# IvoOerlikon2.net
KiCad netlist of a schematic drawn in EAGLE
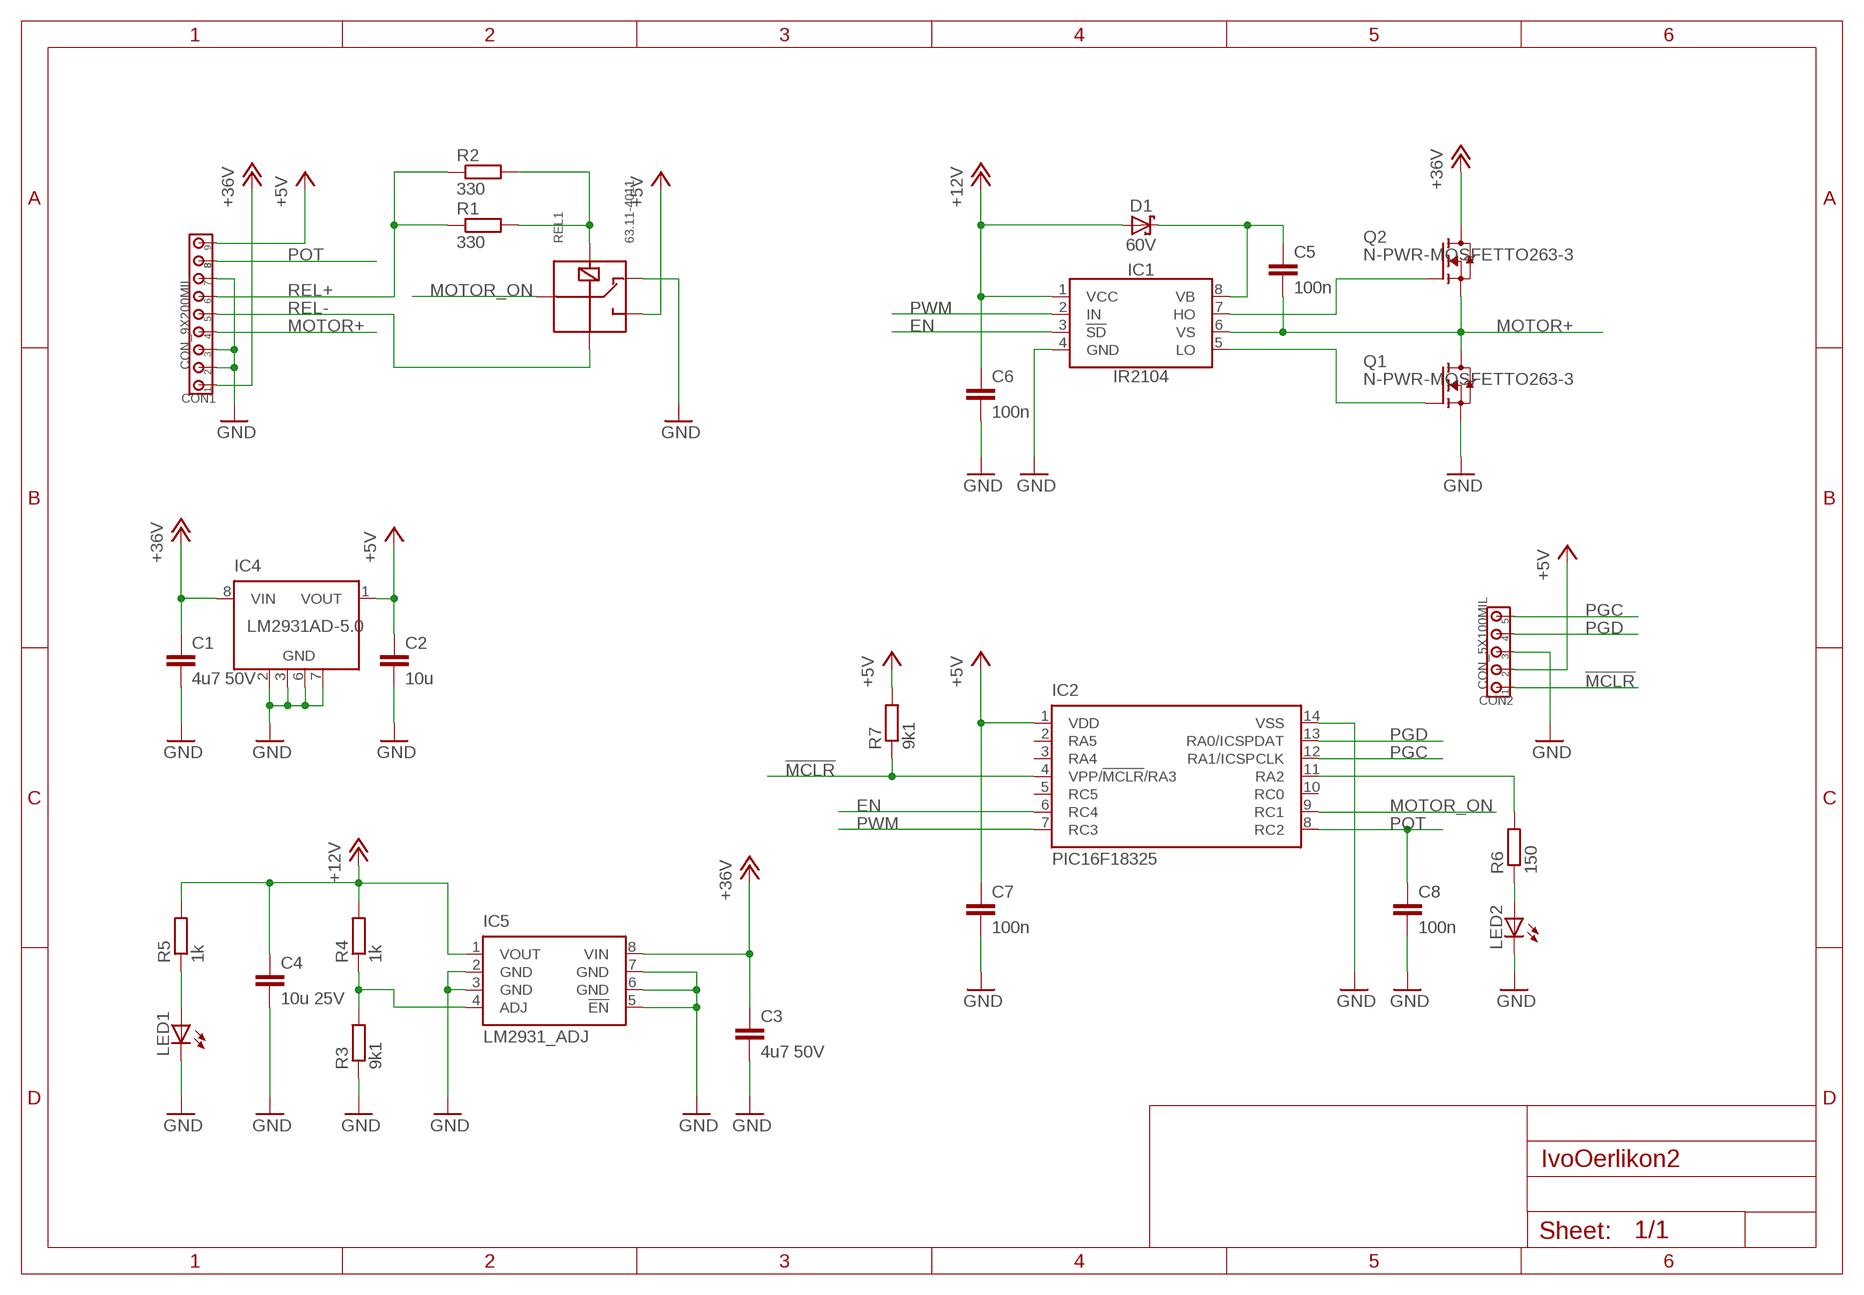
[diagram p0: schematic, sheet 1]

(export (version "E")
  (design (tool "Eeschema 10.0.6"))
  (components
    (comp (ref "C1")
      (value "4u7 50V")
      (footprint "eagle-import:C1206")
      (libsource (lib "eagle-import") (part "CC1206"))
    )
    (comp (ref "C2")
      (value "10u")
      (footprint "eagle-import:C0805")
      (libsource (lib "eagle-import") (part "CC0805"))
    )
    (comp (ref "C3")
      (value "4u7 50V")
      (footprint "eagle-import:C1206")
      (libsource (lib "eagle-import") (part "CC1206"))
    )
    (comp (ref "C4")
      (value "10u 25V")
      (footprint "eagle-import:C1206")
      (libsource (lib "eagle-import") (part "CC1206"))
    )
    (comp (ref "C5")
      (value "100n")
      (footprint "eagle-import:C0805")
      (libsource (lib "eagle-import") (part "CC0805"))
    )
    (comp (ref "C6")
      (value "100n")
      (footprint "eagle-import:C0805")
      (libsource (lib "eagle-import") (part "CC0805"))
    )
    (comp (ref "C7")
      (value "100n")
      (footprint "eagle-import:C0805")
      (libsource (lib "eagle-import") (part "CC0805"))
    )
    (comp (ref "C8")
      (value "100n")
      (footprint "eagle-import:C0805")
      (libsource (lib "eagle-import") (part "CC0805"))
    )
    (comp (ref "CON1")
      (value "CON_9X200MIL")
      (footprint "eagle-import:200MIL_9X")
      (libsource (lib "eagle-import") (part "CON_9X200MIL"))
    )
    (comp (ref "CON2")
      (value "CON_5X100MIL")
      (footprint "eagle-import:100MIL_5X")
      (libsource (lib "eagle-import") (part "CON_5X100MIL"))
    )
    (comp (ref "D1")
      (value "60V")
      (footprint "eagle-import:SOD123")
      (libsource (lib "eagle-import") (part "SCHOTTKYSOD123"))
    )
    (comp (ref "IC1")
      (value "IR2104")
      (footprint "eagle-import:SOIC8")
      (libsource (lib "eagle-import") (part "IR2104"))
    )
    (comp (ref "IC2")
      (value "PIC16F18325")
      (footprint "eagle-import:SO14")
      (libsource (lib "eagle-import") (part "PIC16F18325"))
    )
    (comp (ref "IC4")
      (value "LM2931AD-5.0")
      (footprint "eagle-import:SOIC8")
      (libsource (lib "eagle-import") (part "LM2931AD-5.0"))
    )
    (comp (ref "IC5")
      (value "LM2931_ADJ")
      (footprint "eagle-import:SOIC8")
      (libsource (lib "eagle-import") (part "LM2931_ADJ"))
    )
    (comp (ref "LED1")
      (value "LED0805")
      (footprint "eagle-import:LED0805")
      (libsource (lib "eagle-import") (part "LED0805"))
    )
    (comp (ref "LED2")
      (value "LED0805")
      (footprint "eagle-import:LED0805")
      (libsource (lib "eagle-import") (part "LED0805"))
    )
    (comp (ref "Q1")
      (value "N-PWR-MOSFETTO263-3")
      (footprint "eagle-import:TO263-3")
      (libsource (lib "eagle-import") (part "N-PWR-MOSFETTO263-3"))
    )
    (comp (ref "Q2")
      (value "N-PWR-MOSFETTO263-3")
      (footprint "eagle-import:TO263-3")
      (libsource (lib "eagle-import") (part "N-PWR-MOSFETTO263-3"))
    )
    (comp (ref "R1")
      (value "330")
      (footprint "eagle-import:R1206")
      (libsource (lib "eagle-import") (part "RESISTORR1206"))
    )
    (comp (ref "R2")
      (value "330")
      (footprint "eagle-import:R1206")
      (libsource (lib "eagle-import") (part "RESISTORR1206"))
    )
    (comp (ref "R3")
      (value "9k1")
      (footprint "eagle-import:R0805")
      (libsource (lib "eagle-import") (part "RESISTORR0805"))
    )
    (comp (ref "R4")
      (value "1k")
      (footprint "eagle-import:R0805")
      (libsource (lib "eagle-import") (part "RESISTORR0805"))
    )
    (comp (ref "R5")
      (value "1k")
      (footprint "eagle-import:R0805")
      (libsource (lib "eagle-import") (part "RESISTORR0805"))
    )
    (comp (ref "R6")
      (value "150")
      (footprint "eagle-import:R0805")
      (libsource (lib "eagle-import") (part "RESISTORR0805"))
    )
    (comp (ref "R7")
      (value "9k1")
      (footprint "eagle-import:R0805")
      (libsource (lib "eagle-import") (part "RESISTORR0805"))
    )
    (comp (ref "REL1")
      (value "63.11-4011")
      (footprint "eagle-import:G5LE")
      (libsource (lib "eagle-import") (part "63.11-4011"))
    )
  )
  (nets
    (net (code "1") (name "+5V") (class "Default")
      (node (ref "C2") (pin "1") (pinfunction "1_1") (pintype "passive"))
      (node (ref "C7") (pin "1") (pinfunction "1_1") (pintype "passive"))
      (node (ref "CON1") (pin "9") (pinfunction "P$9_9") (pintype "passive"))
      (node (ref "CON2") (pin "2") (pinfunction "2_2") (pintype "passive"))
      (node (ref "IC2") (pin "1") (pinfunction "VDD_1") (pintype "power_in"))
      (node (ref "IC4") (pin "1") (pinfunction "VOUT_1") (pintype "output"))
      (node (ref "R7") (pin "2") (pinfunction "2_2") (pintype "passive"))
      (node (ref "REL1") (pin "C") (pinfunction "C_C") (pintype "passive"))
    )
    (net (code "2") (name "+12V") (class "Default")
      (node (ref "C4") (pin "1") (pinfunction "1_1") (pintype "passive"))
      (node (ref "C6") (pin "1") (pinfunction "1_1") (pintype "passive"))
      (node (ref "D1") (pin "A") (pinfunction "A_A") (pintype "passive"))
      (node (ref "IC1") (pin "1") (pinfunction "VCC_1") (pintype "input"))
      (node (ref "IC5") (pin "1") (pinfunction "VOUT_1") (pintype "output"))
      (node (ref "R4") (pin "2") (pinfunction "2_2") (pintype "passive"))
      (node (ref "R5") (pin "2") (pinfunction "2_2") (pintype "passive"))
    )
    (net (code "3") (name "+36V") (class "Default")
      (node (ref "C1") (pin "1") (pinfunction "1_1") (pintype "passive"))
      (node (ref "C3") (pin "1") (pinfunction "1_1") (pintype "passive"))
      (node (ref "CON1") (pin "1") (pinfunction "P$1_1") (pintype "passive"))
      (node (ref "IC4") (pin "8") (pinfunction "VIN_8") (pintype "passive"))
      (node (ref "IC5") (pin "8") (pinfunction "VIN_8") (pintype "passive"))
      (node (ref "Q2") (pin "TAB") (pinfunction "D_TAB") (pintype "passive"))
    )
    (net (code "4") (name "/EN") (class "Default")
      (node (ref "IC1") (pin "3") (pinfunction "~{SD}_3") (pintype "input"))
      (node (ref "IC2") (pin "6") (pinfunction "RC4_6") (pintype "bidirectional"))
    )
    (net (code "5") (name "/MOTOR+") (class "Default")
      (node (ref "C5") (pin "2") (pinfunction "2_2") (pintype "passive"))
      (node (ref "CON1") (pin "4") (pinfunction "P$4_4") (pintype "passive"))
      (node (ref "IC1") (pin "6") (pinfunction "VS_6") (pintype "bidirectional"))
      (node (ref "Q1") (pin "TAB") (pinfunction "D_TAB") (pintype "passive"))
      (node (ref "Q2") (pin "3") (pinfunction "S_3") (pintype "passive"))
    )
    (net (code "6") (name "/MOTOR_ON") (class "Default")
      (node (ref "IC2") (pin "9") (pinfunction "RC1_9") (pintype "bidirectional"))
      (node (ref "REL1") (pin "COM") (pinfunction "COM_COM") (pintype "passive"))
    )
    (net (code "7") (name "/PGC") (class "Default")
      (node (ref "CON2") (pin "5") (pinfunction "5_5") (pintype "passive"))
      (node (ref "IC2") (pin "12") (pinfunction "RA1/ICSPCLK_12") (pintype "bidirectional"))
    )
    (net (code "8") (name "/PGD") (class "Default")
      (node (ref "CON2") (pin "4") (pinfunction "4_4") (pintype "passive"))
      (node (ref "IC2") (pin "13") (pinfunction "RA0/ICSPDAT_13") (pintype "bidirectional"))
    )
    (net (code "9") (name "/POT") (class "Default")
      (node (ref "C8") (pin "1") (pinfunction "1_1") (pintype "passive"))
      (node (ref "CON1") (pin "8") (pinfunction "P$8_8") (pintype "passive"))
      (node (ref "IC2") (pin "8") (pinfunction "RC2_8") (pintype "bidirectional"))
    )
    (net (code "10") (name "/PWM") (class "Default")
      (node (ref "IC1") (pin "2") (pinfunction "IN_2") (pintype "input"))
      (node (ref "IC2") (pin "7") (pinfunction "RC3_7") (pintype "bidirectional"))
    )
    (net (code "11") (name "/REL+") (class "Default")
      (node (ref "CON1") (pin "6") (pinfunction "P$6_6") (pintype "passive"))
      (node (ref "R1") (pin "1") (pinfunction "1_1") (pintype "passive"))
      (node (ref "R2") (pin "1") (pinfunction "1_1") (pintype "passive"))
    )
    (net (code "12") (name "/REL-") (class "Default")
      (node (ref "CON1") (pin "5") (pinfunction "P$5_5") (pintype "passive"))
      (node (ref "REL1") (pin "1") (pinfunction "1_1") (pintype "passive"))
    )
    (net (code "13") (name "/~{MCLR}") (class "Default")
      (node (ref "CON2") (pin "1") (pinfunction "1_1") (pintype "passive"))
      (node (ref "IC2") (pin "4") (pinfunction "VPP/~{MCLR}/RA3_4") (pintype "bidirectional"))
      (node (ref "R7") (pin "1") (pinfunction "1_1") (pintype "passive"))
    )
    (net (code "14") (name "GND") (class "Default")
      (node (ref "C1") (pin "2") (pinfunction "2_2") (pintype "passive"))
      (node (ref "C2") (pin "2") (pinfunction "2_2") (pintype "passive"))
      (node (ref "C3") (pin "2") (pinfunction "2_2") (pintype "passive"))
      (node (ref "C4") (pin "2") (pinfunction "2_2") (pintype "passive"))
      (node (ref "C6") (pin "2") (pinfunction "2_2") (pintype "passive"))
      (node (ref "C7") (pin "2") (pinfunction "2_2") (pintype "passive"))
      (node (ref "C8") (pin "2") (pinfunction "2_2") (pintype "passive"))
      (node (ref "CON1") (pin "2") (pinfunction "P$2_2") (pintype "passive"))
      (node (ref "CON1") (pin "3") (pinfunction "P$3_3") (pintype "passive"))
      (node (ref "CON1") (pin "7") (pinfunction "P$7_7") (pintype "passive"))
      (node (ref "CON2") (pin "3") (pinfunction "3_3") (pintype "passive"))
      (node (ref "IC1") (pin "4") (pinfunction "GND_4") (pintype "input"))
      (node (ref "IC2") (pin "14") (pinfunction "VSS_14") (pintype "power_in"))
      (node (ref "IC4") (pin "2") (pinfunction "GND_2") (pintype "power_in"))
      (node (ref "IC4") (pin "3") (pinfunction "GND_3") (pintype "power_in"))
      (node (ref "IC4") (pin "6") (pinfunction "GND_6") (pintype "power_in"))
      (node (ref "IC4") (pin "7") (pinfunction "GND_7") (pintype "power_in"))
      (node (ref "IC5") (pin "2") (pinfunction "GND_2") (pintype "passive"))
      (node (ref "IC5") (pin "3") (pinfunction "GND_3") (pintype "passive"))
      (node (ref "IC5") (pin "5") (pinfunction "~{EN}_5") (pintype "passive"))
      (node (ref "IC5") (pin "6") (pinfunction "GND_6") (pintype "output"))
      (node (ref "IC5") (pin "7") (pinfunction "GND_7") (pintype "output"))
      (node (ref "LED1") (pin "C") (pinfunction "C_C") (pintype "passive"))
      (node (ref "LED2") (pin "C") (pinfunction "C_C") (pintype "passive"))
      (node (ref "Q1") (pin "3") (pinfunction "S_3") (pintype "passive"))
      (node (ref "R3") (pin "1") (pinfunction "1_1") (pintype "passive"))
      (node (ref "REL1") (pin "O") (pinfunction "O_O") (pintype "passive"))
    )
    (net (code "15") (name "Net-(IC1-HO)") (class "Default")
      (node (ref "IC1") (pin "7") (pinfunction "HO_7") (pintype "bidirectional"))
      (node (ref "Q2") (pin "1") (pinfunction "G_1") (pintype "passive"))
    )
    (net (code "16") (name "Net-(IC1-LO)") (class "Default")
      (node (ref "IC1") (pin "5") (pinfunction "LO_5") (pintype "bidirectional"))
      (node (ref "Q1") (pin "1") (pinfunction "G_1") (pintype "passive"))
    )
    (net (code "17") (name "Net-(IC1-VB)") (class "Default")
      (node (ref "C5") (pin "1") (pinfunction "1_1") (pintype "passive"))
      (node (ref "D1") (pin "C") (pinfunction "C_C") (pintype "passive"))
      (node (ref "IC1") (pin "8") (pinfunction "VB_8") (pintype "power_in"))
    )
    (net (code "18") (name "Net-(IC2-RA2)") (class "Default")
      (node (ref "IC2") (pin "11") (pinfunction "RA2_11") (pintype "bidirectional"))
      (node (ref "R6") (pin "2") (pinfunction "2_2") (pintype "passive"))
    )
    (net (code "19") (name "Net-(IC5-ADJ)") (class "Default")
      (node (ref "IC5") (pin "4") (pinfunction "ADJ_4") (pintype "output"))
      (node (ref "R3") (pin "2") (pinfunction "2_2") (pintype "passive"))
      (node (ref "R4") (pin "1") (pinfunction "1_1") (pintype "passive"))
    )
    (net (code "20") (name "Net-(LED1-PadA)") (class "Default")
      (node (ref "LED1") (pin "A") (pinfunction "A_A") (pintype "passive"))
      (node (ref "R5") (pin "1") (pinfunction "1_1") (pintype "passive"))
    )
    (net (code "21") (name "Net-(LED2-PadA)") (class "Default")
      (node (ref "LED2") (pin "A") (pinfunction "A_A") (pintype "passive"))
      (node (ref "R6") (pin "1") (pinfunction "1_1") (pintype "passive"))
    )
    (net (code "22") (name "Net-(R1-Pad2)") (class "Default")
      (node (ref "R1") (pin "2") (pinfunction "2_2") (pintype "passive"))
      (node (ref "R2") (pin "2") (pinfunction "2_2") (pintype "passive"))
      (node (ref "REL1") (pin "2") (pinfunction "2_2") (pintype "passive"))
    )
    (net (code "23") (name "unconnected-(IC2-RA4-Pad3)") (class "Default")
      (node (ref "IC2") (pin "3") (pinfunction "RA4_3") (pintype "bidirectional"))
    )
    (net (code "24") (name "unconnected-(IC2-RA5-Pad2)") (class "Default")
      (node (ref "IC2") (pin "2") (pinfunction "RA5_2") (pintype "input"))
    )
    (net (code "25") (name "unconnected-(IC2-RC0-Pad10)") (class "Default")
      (node (ref "IC2") (pin "10") (pinfunction "RC0_10") (pintype "bidirectional"))
    )
    (net (code "26") (name "unconnected-(IC2-RC5-Pad5)") (class "Default")
      (node (ref "IC2") (pin "5") (pinfunction "RC5_5") (pintype "bidirectional"))
    )
  )
)
